# OPEnS-Power-7_2.net
KiCad netlist of a schematic drawn in EAGLE
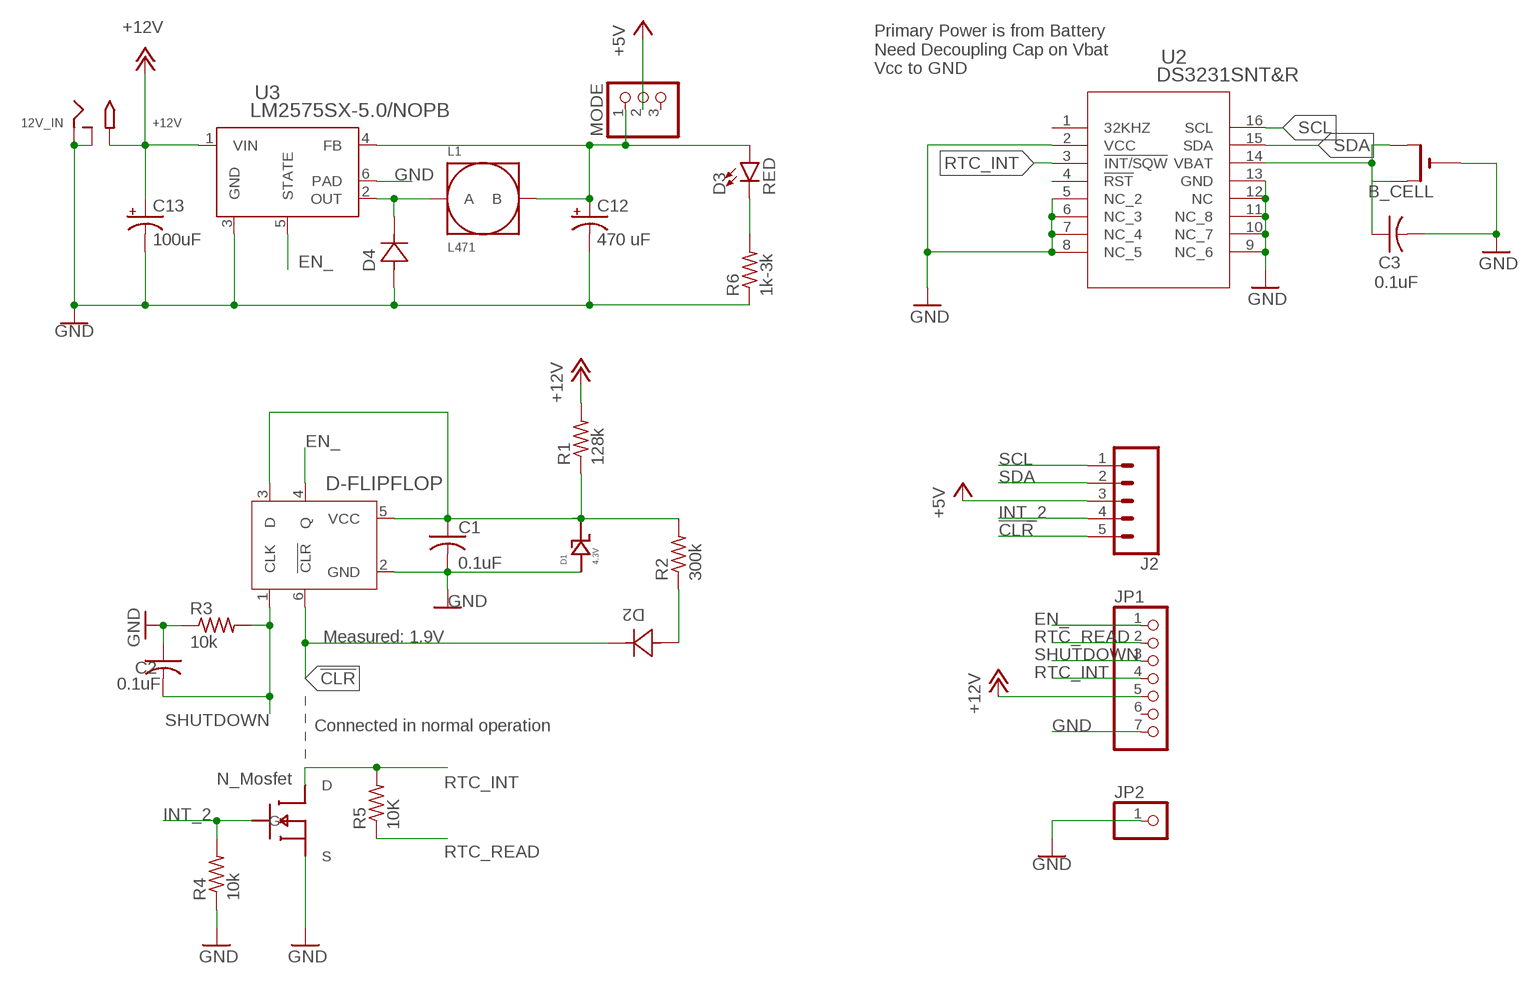
[diagram p0: schematic, sheet 1]

(export (version "E")
  (design (tool "Eeschema 10.0.6"))
  (components
    (comp (ref "12V_IN")
      (value "2.1MMJACKSMT")
      (footprint "eagle-import:DCJACK_2MM_SMT")
      (libsource (lib "eagle-import") (part "2.1MMJACKSMT"))
    )
    (comp (ref "B_CELL")
      (value "CR1220SMT")
      (footprint "eagle-import:CR1220-SMD")
      (libsource (lib "eagle-import") (part "CR1220SMT"))
    )
    (comp (ref "C1")
      (value "0.1uF")
      (footprint "eagle-import:C1206")
      (libsource (lib "eagle-import") (part "C-USC1206"))
    )
    (comp (ref "C2")
      (value "0.1uF")
      (footprint "eagle-import:C1206")
      (libsource (lib "eagle-import") (part "C-USC1206"))
    )
    (comp (ref "C3")
      (value "0.1uF")
      (footprint "eagle-import:C1206")
      (libsource (lib "eagle-import") (part "C-USC1206"))
    )
    (comp (ref "C12")
      (value "470 uF")
      (footprint "eagle-import:153CLV-0810")
      (libsource (lib "eagle-import") (part "rcl_334_CPOL-US153CLV-0810"))
    )
    (comp (ref "C13")
      (value "100uF")
      (footprint "eagle-import:153CLV-0505")
      (libsource (lib "eagle-import") (part "CPOL-US153CLV-0505"))
    )
    (comp (ref "D-FLIPFLOP")
      (value "SN74LVC1G175DBVR")
      (footprint "eagle-import:DBV6")
      (libsource (lib "eagle-import") (part "SN74LVC1G175DBVR"))
    )
    (comp (ref "D1")
      (value "4.3V")
      (footprint "eagle-import:DO-219AC")
      (libsource (lib "eagle-import") (part "ZENER-DO219"))
    )
    (comp (ref "D2")
      (value "S1A-13-F")
      (footprint "eagle-import:SMA")
      (fields (field (name "MANUFACTURER_PART_NUMBER") "S1A13F"))
      (libsource (lib "eagle-import") (part "S1A-13-F"))
    )
    (comp (ref "D3")
      (value "RED")
      (footprint "eagle-import:LED-1206")
      (libsource (lib "eagle-import") (part "LED-RED1206"))
    )
    (comp (ref "D4")
      (value "S1A-13-F")
      (footprint "eagle-import:SMA")
      (fields (field (name "MANUFACTURER_PART_NUMBER") "S1A13F"))
      (libsource (lib "eagle-import") (part "S1A-13-F"))
    )
    (comp (ref "J2")
      (value "CONN_05")
      (footprint "eagle-import:1X05")
      (libsource (lib "eagle-import") (part "CONN_05"))
    )
    (comp (ref "JP1")
      (value "PINHD-1X7")
      (footprint "eagle-import:1X07")
      (libsource (lib "eagle-import") (part "PINHD-1X7"))
    )
    (comp (ref "JP2")
      (value "PINHD-1X1")
      (footprint "eagle-import:1X01")
      (libsource (lib "eagle-import") (part "PINHD-1X1"))
    )
    (comp (ref "L1")
      (value "L471")
      (footprint "eagle-import:12-12")
      (libsource (lib "eagle-import") (part "L471"))
    )
    (comp (ref "MODE")
      (value "PINHD-1X3")
      (footprint "eagle-import:1X03")
      (libsource (lib "eagle-import") (part "PINHD-1X3"))
    )
    (comp (ref "MOSFET")
      (value "MOSFET-SOT23F")
      (footprint "eagle-import:SOT-23F")
      (libsource (lib "eagle-import") (part "MOSFET-SOT23F"))
    )
    (comp (ref "R1")
      (value "128k")
      (footprint "eagle-import:R1206")
      (libsource (lib "eagle-import") (part "R-US_R1206"))
    )
    (comp (ref "R2")
      (value "300k")
      (footprint "eagle-import:R1206")
      (libsource (lib "eagle-import") (part "R-US_R1206"))
    )
    (comp (ref "R3")
      (value "10k")
      (footprint "eagle-import:R1206")
      (libsource (lib "eagle-import") (part "R-US_R1206"))
    )
    (comp (ref "R4")
      (value "10k")
      (footprint "eagle-import:R1206")
      (libsource (lib "eagle-import") (part "R-US_R1206"))
    )
    (comp (ref "R5")
      (value "10K")
      (footprint "eagle-import:R1206")
      (libsource (lib "eagle-import") (part "R-US_R1206"))
    )
    (comp (ref "R6")
      (value "1k-3k")
      (footprint "eagle-import:R1206")
      (libsource (lib "eagle-import") (part "R-US_R1206"))
    )
    (comp (ref "U2")
      (value "DS3231SNT&R")
      (footprint "eagle-import:21-0042B_16")
      (fields (field (name "MANUFACTURER_PART_NUMBER") "DS3231SN#T&R"))
      (libsource (lib "eagle-import") (part "DS3231SNT&R"))
    )
    (comp (ref "U3")
      (value "LM2575SX-5.0/NOPB")
      (footprint "eagle-import:KTT0005B")
      (fields (field (name "MANUFACTURER_PART_NUMBER") "LM2575SX5.0NOPB"))
      (libsource (lib "eagle-import") (part "LM2575SX-5.0/NOPB"))
    )
  )
  (nets
    (net (code "1") (name "+5V") (class "Default")
      (node (ref "J2") (pin "3") (pinfunction "3_3") (pintype "passive"))
      (node (ref "MODE") (pin "2") (pinfunction "2_2") (pintype "passive"))
    )
    (net (code "2") (name "+12V") (class "Default")
      (node (ref "12V_IN") (pin "PWR2") (pinfunction "TIP_PWR2") (pintype "bidirectional"))
      (node (ref "C13") (pin "+") (pinfunction "+_+") (pintype "passive"))
      (node (ref "JP1") (pin "5") (pinfunction "5_5") (pintype "passive"))
      (node (ref "R1") (pin "2") (pinfunction "2_2") (pintype "passive"))
      (node (ref "U3") (pin "1") (pinfunction "VIN_1") (pintype "power_in"))
    )
    (net (code "3") (name "/EN_") (class "Default")
      (node (ref "D-FLIPFLOP") (pin "4") (pinfunction "Q_4") (pintype "output"))
      (node (ref "JP1") (pin "1") (pinfunction "1_1") (pintype "passive"))
      (node (ref "U3") (pin "5") (pinfunction "STATE_5") (pintype "input"))
    )
    (net (code "4") (name "/INT_2") (class "Default")
      (node (ref "J2") (pin "4") (pinfunction "4_4") (pintype "passive"))
      (node (ref "MOSFET") (pin "G") (pinfunction "G_G") (pintype "bidirectional"))
      (node (ref "R4") (pin "2") (pinfunction "2_2") (pintype "passive"))
    )
    (net (code "5") (name "/RTC_READ") (class "Default")
      (node (ref "JP1") (pin "2") (pinfunction "2_2") (pintype "passive"))
      (node (ref "R5") (pin "1") (pinfunction "1_1") (pintype "passive"))
    )
    (net (code "6") (name "/SHUTDOWN") (class "Default")
      (node (ref "C2") (pin "2") (pinfunction "2_2") (pintype "passive"))
      (node (ref "D-FLIPFLOP") (pin "1") (pinfunction "CLK_1") (pintype "input"))
      (node (ref "JP1") (pin "3") (pinfunction "3_3") (pintype "passive"))
      (node (ref "R3") (pin "2") (pinfunction "2_2") (pintype "passive"))
    )
    (net (code "7") (name "/~{CLR}") (class "Default")
      (node (ref "D-FLIPFLOP") (pin "6") (pinfunction "~{CLR}_6") (pintype "input"))
      (node (ref "D2") (pin "1") (pinfunction "1_1") (pintype "passive"))
      (node (ref "J2") (pin "5") (pinfunction "5_5") (pintype "passive"))
    )
    (net (code "8") (name "GND") (class "Default")
      (node (ref "12V_IN") (pin "GND") (pinfunction "RING_GND") (pintype "bidirectional"))
      (node (ref "12V_IN") (pin "GNDBREAK") (pinfunction "RING_SW_GNDBREAK") (pintype "bidirectional"))
      (node (ref "B_CELL") (pin "-") (pinfunction "-_-") (pintype "passive"))
      (node (ref "C1") (pin "2") (pinfunction "2_2") (pintype "passive"))
      (node (ref "C12") (pin "-") (pinfunction "-_-") (pintype "passive"))
      (node (ref "C13") (pin "-") (pinfunction "-_-") (pintype "passive"))
      (node (ref "C2") (pin "1") (pinfunction "1_1") (pintype "passive"))
      (node (ref "C3") (pin "2") (pinfunction "2_2") (pintype "passive"))
      (node (ref "D-FLIPFLOP") (pin "2") (pinfunction "GND_2") (pintype "power_in"))
      (node (ref "D1") (pin "BCK") (pinfunction "BCK_BCK") (pintype "bidirectional"))
      (node (ref "D4") (pin "2") (pinfunction "2_2") (pintype "passive"))
      (node (ref "JP1") (pin "7") (pinfunction "7_7") (pintype "passive"))
      (node (ref "JP2") (pin "1") (pinfunction "1_1") (pintype "passive"))
      (node (ref "MOSFET") (pin "S") (pinfunction "S_S") (pintype "bidirectional"))
      (node (ref "R3") (pin "1") (pinfunction "1_1") (pintype "passive"))
      (node (ref "R4") (pin "1") (pinfunction "1_1") (pintype "passive"))
      (node (ref "R6") (pin "1") (pinfunction "1_1") (pintype "passive"))
      (node (ref "U2") (pin "10") (pinfunction "NC_7_10") (pintype "passive"))
      (node (ref "U2") (pin "11") (pinfunction "NC_8_11") (pintype "passive"))
      (node (ref "U2") (pin "12") (pinfunction "NC_12") (pintype "passive"))
      (node (ref "U2") (pin "13") (pinfunction "GND_13") (pintype "power_in"))
      (node (ref "U2") (pin "2") (pinfunction "VCC_2") (pintype "power_in"))
      (node (ref "U2") (pin "5") (pinfunction "NC_2_5") (pintype "passive"))
      (node (ref "U2") (pin "6") (pinfunction "NC_3_6") (pintype "passive"))
      (node (ref "U2") (pin "7") (pinfunction "NC_4_7") (pintype "passive"))
      (node (ref "U2") (pin "8") (pinfunction "NC_5_8") (pintype "passive"))
      (node (ref "U2") (pin "9") (pinfunction "NC_6_9") (pintype "passive"))
      (node (ref "U3") (pin "3") (pinfunction "GND_3") (pintype "power_in"))
      (node (ref "U3") (pin "6") (pinfunction "PAD_6") (pintype "passive"))
    )
    (net (code "9") (name "Net-(B_CELL-+)") (class "Default")
      (node (ref "B_CELL") (pin "+$1") (pinfunction "+_+$1") (pintype "passive"))
      (node (ref "B_CELL") (pin "+$2") (pinfunction "+1_+$2") (pintype "passive"))
      (node (ref "C3") (pin "1") (pinfunction "1_1") (pintype "passive"))
      (node (ref "U2") (pin "14") (pinfunction "VBAT_14") (pintype "power_in"))
    )
    (net (code "10") (name "Net-(D-FLIPFLOP-D)") (class "Default")
      (node (ref "C1") (pin "1") (pinfunction "1_1") (pintype "passive"))
      (node (ref "D-FLIPFLOP") (pin "3") (pinfunction "D_3") (pintype "input"))
      (node (ref "D-FLIPFLOP") (pin "5") (pinfunction "VCC_5") (pintype "power_in"))
      (node (ref "D1") (pin "FNT") (pinfunction "FNT_FNT") (pintype "bidirectional"))
      (node (ref "R1") (pin "1") (pinfunction "1_1") (pintype "passive"))
      (node (ref "R2") (pin "2") (pinfunction "2_2") (pintype "passive"))
    )
    (net (code "11") (name "Net-(D2-Pad2)") (class "Default")
      (node (ref "D2") (pin "2") (pinfunction "2_2") (pintype "passive"))
      (node (ref "R2") (pin "1") (pinfunction "1_1") (pintype "passive"))
    )
    (net (code "12") (name "Net-(D3-PadC)") (class "Default")
      (node (ref "D3") (pin "C") (pinfunction "C_C") (pintype "passive"))
      (node (ref "R6") (pin "2") (pinfunction "2_2") (pintype "passive"))
    )
    (net (code "13") (name "Net-(U3-FB)") (class "Default")
      (node (ref "C12") (pin "+") (pinfunction "+_+") (pintype "passive"))
      (node (ref "D3") (pin "A") (pinfunction "A_A") (pintype "passive"))
      (node (ref "L1") (pin "B") (pinfunction "B_B") (pintype "bidirectional"))
      (node (ref "MODE") (pin "1") (pinfunction "1_1") (pintype "passive"))
      (node (ref "U3") (pin "4") (pinfunction "FB_4") (pintype "input"))
    )
    (net (code "14") (name "Net-(U3-OUT)") (class "Default")
      (node (ref "D4") (pin "1") (pinfunction "1_1") (pintype "passive"))
      (node (ref "L1") (pin "A") (pinfunction "A_A") (pintype "bidirectional"))
      (node (ref "U3") (pin "2") (pinfunction "OUT_2") (pintype "output"))
    )
    (net (code "15") (name "RTC_INT") (class "Default")
      (node (ref "JP1") (pin "4") (pinfunction "4_4") (pintype "passive"))
      (node (ref "MOSFET") (pin "D") (pinfunction "D_D") (pintype "bidirectional"))
      (node (ref "R5") (pin "2") (pinfunction "2_2") (pintype "passive"))
      (node (ref "U2") (pin "3") (pinfunction "~{INT/SQW}_3") (pintype "passive"))
    )
    (net (code "16") (name "SCL") (class "Default")
      (node (ref "J2") (pin "1") (pinfunction "1_1") (pintype "passive"))
      (node (ref "U2") (pin "16") (pinfunction "SCL_16") (pintype "passive"))
    )
    (net (code "17") (name "SDA") (class "Default")
      (node (ref "J2") (pin "2") (pinfunction "2_2") (pintype "passive"))
      (node (ref "U2") (pin "15") (pinfunction "SDA_15") (pintype "passive"))
    )
    (net (code "18") (name "unconnected-(JP1-Pad6)") (class "Default")
      (node (ref "JP1") (pin "6") (pinfunction "6_6") (pintype "passive"))
    )
    (net (code "19") (name "unconnected-(MODE-Pad3)") (class "Default")
      (node (ref "MODE") (pin "3") (pinfunction "3_3") (pintype "passive"))
    )
    (net (code "20") (name "unconnected-(U2-32KHZ-Pad1)") (class "Default")
      (node (ref "U2") (pin "1") (pinfunction "32KHZ_1") (pintype "passive"))
    )
    (net (code "21") (name "unconnected-(U2-~{RST}-Pad4)") (class "Default")
      (node (ref "U2") (pin "4") (pinfunction "~{RST}_4") (pintype "passive"))
    )
  )
)
